# lp_breadboard_mini.net
KiCad netlist of a schematic drawn in EAGLE
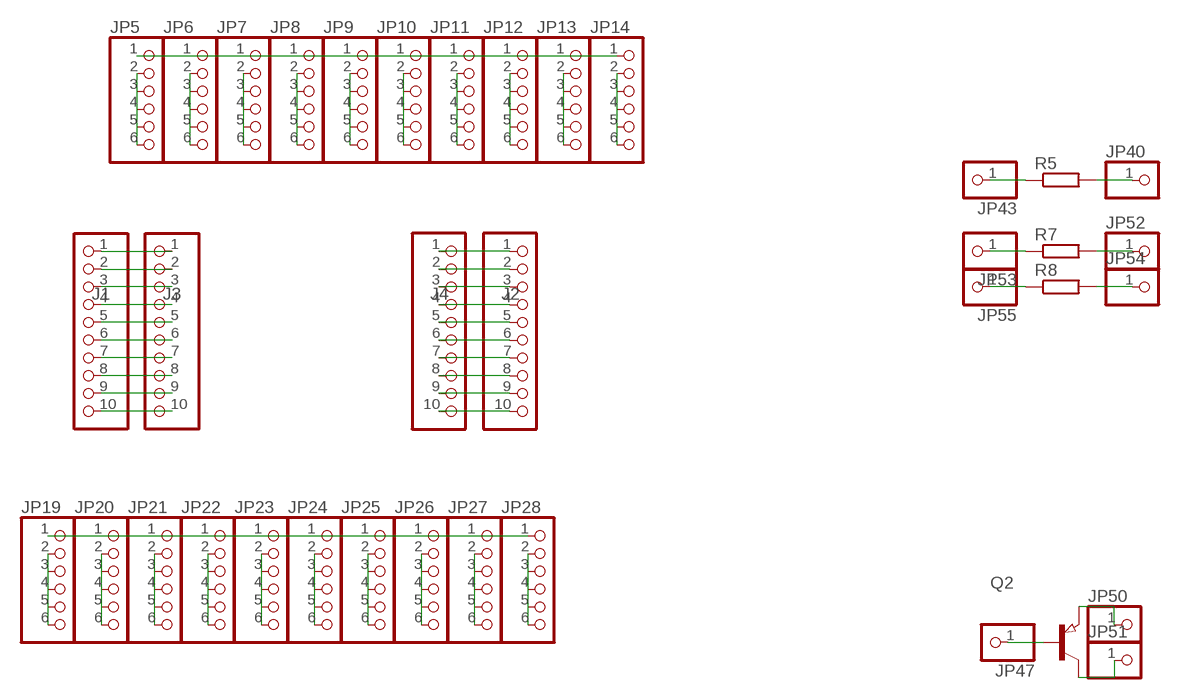
[diagram p0: schematic, sheet 1]

(export (version "E")
  (design (tool "Eeschema 10.0.6"))
  (components
    (comp (ref "J1")
      (value "PINHD-1X10")
      (footprint "eagle-import:1X10")
      (libsource (lib "eagle-import") (part "PINHD-1X10"))
    )
    (comp (ref "J2")
      (value "PINHD-1X10")
      (footprint "eagle-import:1X10")
      (libsource (lib "eagle-import") (part "PINHD-1X10"))
    )
    (comp (ref "J3")
      (value "PINHD-1X10")
      (footprint "eagle-import:1X10")
      (libsource (lib "eagle-import") (part "PINHD-1X10"))
    )
    (comp (ref "J4")
      (value "PINHD-1X10")
      (footprint "eagle-import:1X10")
      (libsource (lib "eagle-import") (part "PINHD-1X10"))
    )
    (comp (ref "JP5")
      (value "PINHD-1X6")
      (footprint "eagle-import:1X06")
      (libsource (lib "eagle-import") (part "PINHD-1X6"))
    )
    (comp (ref "JP6")
      (value "PINHD-1X6")
      (footprint "eagle-import:1X06")
      (libsource (lib "eagle-import") (part "PINHD-1X6"))
    )
    (comp (ref "JP7")
      (value "PINHD-1X6")
      (footprint "eagle-import:1X06")
      (libsource (lib "eagle-import") (part "PINHD-1X6"))
    )
    (comp (ref "JP8")
      (value "PINHD-1X6")
      (footprint "eagle-import:1X06")
      (libsource (lib "eagle-import") (part "PINHD-1X6"))
    )
    (comp (ref "JP9")
      (value "PINHD-1X6")
      (footprint "eagle-import:1X06")
      (libsource (lib "eagle-import") (part "PINHD-1X6"))
    )
    (comp (ref "JP10")
      (value "PINHD-1X6")
      (footprint "eagle-import:1X06")
      (libsource (lib "eagle-import") (part "PINHD-1X6"))
    )
    (comp (ref "JP11")
      (value "PINHD-1X6")
      (footprint "eagle-import:1X06")
      (libsource (lib "eagle-import") (part "PINHD-1X6"))
    )
    (comp (ref "JP12")
      (value "PINHD-1X6")
      (footprint "eagle-import:1X06")
      (libsource (lib "eagle-import") (part "PINHD-1X6"))
    )
    (comp (ref "JP13")
      (value "PINHD-1X6")
      (footprint "eagle-import:1X06")
      (libsource (lib "eagle-import") (part "PINHD-1X6"))
    )
    (comp (ref "JP14")
      (value "PINHD-1X6")
      (footprint "eagle-import:1X06")
      (libsource (lib "eagle-import") (part "PINHD-1X6"))
    )
    (comp (ref "JP19")
      (value "PINHD-1X6")
      (footprint "eagle-import:1X06")
      (libsource (lib "eagle-import") (part "PINHD-1X6"))
    )
    (comp (ref "JP20")
      (value "PINHD-1X6")
      (footprint "eagle-import:1X06")
      (libsource (lib "eagle-import") (part "PINHD-1X6"))
    )
    (comp (ref "JP21")
      (value "PINHD-1X6")
      (footprint "eagle-import:1X06")
      (libsource (lib "eagle-import") (part "PINHD-1X6"))
    )
    (comp (ref "JP22")
      (value "PINHD-1X6")
      (footprint "eagle-import:1X06")
      (libsource (lib "eagle-import") (part "PINHD-1X6"))
    )
    (comp (ref "JP23")
      (value "PINHD-1X6")
      (footprint "eagle-import:1X06")
      (libsource (lib "eagle-import") (part "PINHD-1X6"))
    )
    (comp (ref "JP24")
      (value "PINHD-1X6")
      (footprint "eagle-import:1X06")
      (libsource (lib "eagle-import") (part "PINHD-1X6"))
    )
    (comp (ref "JP25")
      (value "PINHD-1X6")
      (footprint "eagle-import:1X06")
      (libsource (lib "eagle-import") (part "PINHD-1X6"))
    )
    (comp (ref "JP26")
      (value "PINHD-1X6")
      (footprint "eagle-import:1X06")
      (libsource (lib "eagle-import") (part "PINHD-1X6"))
    )
    (comp (ref "JP27")
      (value "PINHD-1X6")
      (footprint "eagle-import:1X06")
      (libsource (lib "eagle-import") (part "PINHD-1X6"))
    )
    (comp (ref "JP28")
      (value "PINHD-1X6")
      (footprint "eagle-import:1X06")
      (libsource (lib "eagle-import") (part "PINHD-1X6"))
    )
    (comp (ref "JP40")
      (value "PINHD-1X1")
      (footprint "eagle-import:1X01")
      (libsource (lib "eagle-import") (part "PINHD-1X1"))
    )
    (comp (ref "JP43")
      (value "PINHD-1X1")
      (footprint "eagle-import:1X01")
      (libsource (lib "eagle-import") (part "PINHD-1X1"))
    )
    (comp (ref "JP47")
      (value "PINHD-1X1")
      (footprint "eagle-import:1X01")
      (libsource (lib "eagle-import") (part "PINHD-1X1"))
    )
    (comp (ref "JP50")
      (value "PINHD-1X1")
      (footprint "eagle-import:1X01")
      (libsource (lib "eagle-import") (part "PINHD-1X1"))
    )
    (comp (ref "JP51")
      (value "PINHD-1X1")
      (footprint "eagle-import:1X01")
      (libsource (lib "eagle-import") (part "PINHD-1X1"))
    )
    (comp (ref "JP52")
      (value "PINHD-1X1")
      (footprint "eagle-import:1X01")
      (libsource (lib "eagle-import") (part "PINHD-1X1"))
    )
    (comp (ref "JP53")
      (value "PINHD-1X1")
      (footprint "eagle-import:1X01")
      (libsource (lib "eagle-import") (part "PINHD-1X1"))
    )
    (comp (ref "JP54")
      (value "PINHD-1X1")
      (footprint "eagle-import:1X01")
      (libsource (lib "eagle-import") (part "PINHD-1X1"))
    )
    (comp (ref "JP55")
      (value "PINHD-1X1")
      (footprint "eagle-import:1X01")
      (libsource (lib "eagle-import") (part "PINHD-1X1"))
    )
    (comp (ref "Q2")
      (value "PNP-TRANSISTOR_SOT23")
      (footprint "eagle-import:SOT23")
      (libsource (lib "eagle-import") (part "PNP-TRANSISTOR_SOT23"))
    )
    (comp (ref "R5")
      (value "R-EU_R0805")
      (footprint "eagle-import:R0805")
      (libsource (lib "eagle-import") (part "R-EU_R0805"))
    )
    (comp (ref "R7")
      (value "R-EU_R0805")
      (footprint "eagle-import:R0805")
      (libsource (lib "eagle-import") (part "R-EU_R0805"))
    )
    (comp (ref "R8")
      (value "R-EU_R0805")
      (footprint "eagle-import:R0805")
      (libsource (lib "eagle-import") (part "R-EU_R0805"))
    )
  )
  (nets
    (net (code "1") (name "/GND") (class "Default")
      (node (ref "J2") (pin "1") (pinfunction "1_1") (pintype "passive"))
      (node (ref "J4") (pin "1") (pinfunction "1_1") (pintype "passive"))
      (node (ref "JP10") (pin "1") (pinfunction "1_1") (pintype "passive"))
      (node (ref "JP11") (pin "1") (pinfunction "1_1") (pintype "passive"))
      (node (ref "JP12") (pin "1") (pinfunction "1_1") (pintype "passive"))
      (node (ref "JP13") (pin "1") (pinfunction "1_1") (pintype "passive"))
      (node (ref "JP14") (pin "1") (pinfunction "1_1") (pintype "passive"))
      (node (ref "JP5") (pin "1") (pinfunction "1_1") (pintype "passive"))
      (node (ref "JP6") (pin "1") (pinfunction "1_1") (pintype "passive"))
      (node (ref "JP7") (pin "1") (pinfunction "1_1") (pintype "passive"))
      (node (ref "JP8") (pin "1") (pinfunction "1_1") (pintype "passive"))
      (node (ref "JP9") (pin "1") (pinfunction "1_1") (pintype "passive"))
    )
    (net (code "2") (name "/VCC") (class "Default")
      (node (ref "J1") (pin "1") (pinfunction "1_1") (pintype "passive"))
      (node (ref "J3") (pin "1") (pinfunction "1_1") (pintype "passive"))
      (node (ref "JP19") (pin "1") (pinfunction "1_1") (pintype "passive"))
      (node (ref "JP20") (pin "1") (pinfunction "1_1") (pintype "passive"))
      (node (ref "JP21") (pin "1") (pinfunction "1_1") (pintype "passive"))
      (node (ref "JP22") (pin "1") (pinfunction "1_1") (pintype "passive"))
      (node (ref "JP23") (pin "1") (pinfunction "1_1") (pintype "passive"))
      (node (ref "JP24") (pin "1") (pinfunction "1_1") (pintype "passive"))
      (node (ref "JP25") (pin "1") (pinfunction "1_1") (pintype "passive"))
      (node (ref "JP26") (pin "1") (pinfunction "1_1") (pintype "passive"))
      (node (ref "JP27") (pin "1") (pinfunction "1_1") (pintype "passive"))
      (node (ref "JP28") (pin "1") (pinfunction "1_1") (pintype "passive"))
    )
    (net (code "3") (name "Net-(J1-Pad2)") (class "Default")
      (node (ref "J1") (pin "2") (pinfunction "2_2") (pintype "passive"))
      (node (ref "J3") (pin "2") (pinfunction "2_2") (pintype "passive"))
    )
    (net (code "4") (name "Net-(J1-Pad3)") (class "Default")
      (node (ref "J1") (pin "3") (pinfunction "3_3") (pintype "passive"))
      (node (ref "J3") (pin "3") (pinfunction "3_3") (pintype "passive"))
    )
    (net (code "5") (name "Net-(J1-Pad4)") (class "Default")
      (node (ref "J1") (pin "4") (pinfunction "4_4") (pintype "passive"))
      (node (ref "J3") (pin "4") (pinfunction "4_4") (pintype "passive"))
    )
    (net (code "6") (name "Net-(J1-Pad5)") (class "Default")
      (node (ref "J1") (pin "5") (pinfunction "5_5") (pintype "passive"))
      (node (ref "J3") (pin "5") (pinfunction "5_5") (pintype "passive"))
    )
    (net (code "7") (name "Net-(J1-Pad6)") (class "Default")
      (node (ref "J1") (pin "6") (pinfunction "6_6") (pintype "passive"))
      (node (ref "J3") (pin "6") (pinfunction "6_6") (pintype "passive"))
    )
    (net (code "8") (name "Net-(J1-Pad7)") (class "Default")
      (node (ref "J1") (pin "7") (pinfunction "7_7") (pintype "passive"))
      (node (ref "J3") (pin "7") (pinfunction "7_7") (pintype "passive"))
    )
    (net (code "9") (name "Net-(J1-Pad8)") (class "Default")
      (node (ref "J1") (pin "8") (pinfunction "8_8") (pintype "passive"))
      (node (ref "J3") (pin "8") (pinfunction "8_8") (pintype "passive"))
    )
    (net (code "10") (name "Net-(J1-Pad9)") (class "Default")
      (node (ref "J1") (pin "9") (pinfunction "9_9") (pintype "passive"))
      (node (ref "J3") (pin "9") (pinfunction "9_9") (pintype "passive"))
    )
    (net (code "11") (name "Net-(J1-Pad10)") (class "Default")
      (node (ref "J1") (pin "10") (pinfunction "10_10") (pintype "passive"))
      (node (ref "J3") (pin "10") (pinfunction "10_10") (pintype "passive"))
    )
    (net (code "12") (name "Net-(J2-Pad2)") (class "Default")
      (node (ref "J2") (pin "2") (pinfunction "2_2") (pintype "passive"))
      (node (ref "J4") (pin "2") (pinfunction "2_2") (pintype "passive"))
    )
    (net (code "13") (name "Net-(J2-Pad3)") (class "Default")
      (node (ref "J2") (pin "3") (pinfunction "3_3") (pintype "passive"))
      (node (ref "J4") (pin "3") (pinfunction "3_3") (pintype "passive"))
    )
    (net (code "14") (name "Net-(J2-Pad4)") (class "Default")
      (node (ref "J2") (pin "4") (pinfunction "4_4") (pintype "passive"))
      (node (ref "J4") (pin "4") (pinfunction "4_4") (pintype "passive"))
    )
    (net (code "15") (name "Net-(J2-Pad5)") (class "Default")
      (node (ref "J2") (pin "5") (pinfunction "5_5") (pintype "passive"))
      (node (ref "J4") (pin "5") (pinfunction "5_5") (pintype "passive"))
    )
    (net (code "16") (name "Net-(J2-Pad6)") (class "Default")
      (node (ref "J2") (pin "6") (pinfunction "6_6") (pintype "passive"))
      (node (ref "J4") (pin "6") (pinfunction "6_6") (pintype "passive"))
    )
    (net (code "17") (name "Net-(J2-Pad7)") (class "Default")
      (node (ref "J2") (pin "7") (pinfunction "7_7") (pintype "passive"))
      (node (ref "J4") (pin "7") (pinfunction "7_7") (pintype "passive"))
    )
    (net (code "18") (name "Net-(J2-Pad8)") (class "Default")
      (node (ref "J2") (pin "8") (pinfunction "8_8") (pintype "passive"))
      (node (ref "J4") (pin "8") (pinfunction "8_8") (pintype "passive"))
    )
    (net (code "19") (name "Net-(J2-Pad9)") (class "Default")
      (node (ref "J2") (pin "9") (pinfunction "9_9") (pintype "passive"))
      (node (ref "J4") (pin "9") (pinfunction "9_9") (pintype "passive"))
    )
    (net (code "20") (name "Net-(J2-Pad10)") (class "Default")
      (node (ref "J2") (pin "10") (pinfunction "10_10") (pintype "passive"))
      (node (ref "J4") (pin "10") (pinfunction "10_10") (pintype "passive"))
    )
    (net (code "21") (name "Net-(JP5-Pad2)") (class "Default")
      (node (ref "JP5") (pin "2") (pinfunction "2_2") (pintype "passive"))
      (node (ref "JP5") (pin "3") (pinfunction "3_3") (pintype "passive"))
      (node (ref "JP5") (pin "4") (pinfunction "4_4") (pintype "passive"))
      (node (ref "JP5") (pin "5") (pinfunction "5_5") (pintype "passive"))
      (node (ref "JP5") (pin "6") (pinfunction "6_6") (pintype "passive"))
    )
    (net (code "22") (name "Net-(JP6-Pad2)") (class "Default")
      (node (ref "JP6") (pin "2") (pinfunction "2_2") (pintype "passive"))
      (node (ref "JP6") (pin "3") (pinfunction "3_3") (pintype "passive"))
      (node (ref "JP6") (pin "4") (pinfunction "4_4") (pintype "passive"))
      (node (ref "JP6") (pin "5") (pinfunction "5_5") (pintype "passive"))
      (node (ref "JP6") (pin "6") (pinfunction "6_6") (pintype "passive"))
    )
    (net (code "23") (name "Net-(JP7-Pad2)") (class "Default")
      (node (ref "JP7") (pin "2") (pinfunction "2_2") (pintype "passive"))
      (node (ref "JP7") (pin "3") (pinfunction "3_3") (pintype "passive"))
      (node (ref "JP7") (pin "4") (pinfunction "4_4") (pintype "passive"))
      (node (ref "JP7") (pin "5") (pinfunction "5_5") (pintype "passive"))
      (node (ref "JP7") (pin "6") (pinfunction "6_6") (pintype "passive"))
    )
    (net (code "24") (name "Net-(JP8-Pad2)") (class "Default")
      (node (ref "JP8") (pin "2") (pinfunction "2_2") (pintype "passive"))
      (node (ref "JP8") (pin "3") (pinfunction "3_3") (pintype "passive"))
      (node (ref "JP8") (pin "4") (pinfunction "4_4") (pintype "passive"))
      (node (ref "JP8") (pin "5") (pinfunction "5_5") (pintype "passive"))
      (node (ref "JP8") (pin "6") (pinfunction "6_6") (pintype "passive"))
    )
    (net (code "25") (name "Net-(JP9-Pad2)") (class "Default")
      (node (ref "JP9") (pin "2") (pinfunction "2_2") (pintype "passive"))
      (node (ref "JP9") (pin "3") (pinfunction "3_3") (pintype "passive"))
      (node (ref "JP9") (pin "4") (pinfunction "4_4") (pintype "passive"))
      (node (ref "JP9") (pin "5") (pinfunction "5_5") (pintype "passive"))
      (node (ref "JP9") (pin "6") (pinfunction "6_6") (pintype "passive"))
    )
    (net (code "26") (name "Net-(JP10-Pad2)") (class "Default")
      (node (ref "JP10") (pin "2") (pinfunction "2_2") (pintype "passive"))
      (node (ref "JP10") (pin "3") (pinfunction "3_3") (pintype "passive"))
      (node (ref "JP10") (pin "4") (pinfunction "4_4") (pintype "passive"))
      (node (ref "JP10") (pin "5") (pinfunction "5_5") (pintype "passive"))
      (node (ref "JP10") (pin "6") (pinfunction "6_6") (pintype "passive"))
    )
    (net (code "27") (name "Net-(JP11-Pad2)") (class "Default")
      (node (ref "JP11") (pin "2") (pinfunction "2_2") (pintype "passive"))
      (node (ref "JP11") (pin "3") (pinfunction "3_3") (pintype "passive"))
      (node (ref "JP11") (pin "4") (pinfunction "4_4") (pintype "passive"))
      (node (ref "JP11") (pin "5") (pinfunction "5_5") (pintype "passive"))
      (node (ref "JP11") (pin "6") (pinfunction "6_6") (pintype "passive"))
    )
    (net (code "28") (name "Net-(JP12-Pad2)") (class "Default")
      (node (ref "JP12") (pin "2") (pinfunction "2_2") (pintype "passive"))
      (node (ref "JP12") (pin "3") (pinfunction "3_3") (pintype "passive"))
      (node (ref "JP12") (pin "4") (pinfunction "4_4") (pintype "passive"))
      (node (ref "JP12") (pin "5") (pinfunction "5_5") (pintype "passive"))
      (node (ref "JP12") (pin "6") (pinfunction "6_6") (pintype "passive"))
    )
    (net (code "29") (name "Net-(JP13-Pad2)") (class "Default")
      (node (ref "JP13") (pin "2") (pinfunction "2_2") (pintype "passive"))
      (node (ref "JP13") (pin "3") (pinfunction "3_3") (pintype "passive"))
      (node (ref "JP13") (pin "4") (pinfunction "4_4") (pintype "passive"))
      (node (ref "JP13") (pin "5") (pinfunction "5_5") (pintype "passive"))
      (node (ref "JP13") (pin "6") (pinfunction "6_6") (pintype "passive"))
    )
    (net (code "30") (name "Net-(JP14-Pad2)") (class "Default")
      (node (ref "JP14") (pin "2") (pinfunction "2_2") (pintype "passive"))
      (node (ref "JP14") (pin "3") (pinfunction "3_3") (pintype "passive"))
      (node (ref "JP14") (pin "4") (pinfunction "4_4") (pintype "passive"))
      (node (ref "JP14") (pin "5") (pinfunction "5_5") (pintype "passive"))
      (node (ref "JP14") (pin "6") (pinfunction "6_6") (pintype "passive"))
    )
    (net (code "31") (name "Net-(JP19-Pad2)") (class "Default")
      (node (ref "JP19") (pin "2") (pinfunction "2_2") (pintype "passive"))
      (node (ref "JP19") (pin "3") (pinfunction "3_3") (pintype "passive"))
      (node (ref "JP19") (pin "4") (pinfunction "4_4") (pintype "passive"))
      (node (ref "JP19") (pin "5") (pinfunction "5_5") (pintype "passive"))
      (node (ref "JP19") (pin "6") (pinfunction "6_6") (pintype "passive"))
    )
    (net (code "32") (name "Net-(JP20-Pad2)") (class "Default")
      (node (ref "JP20") (pin "2") (pinfunction "2_2") (pintype "passive"))
      (node (ref "JP20") (pin "3") (pinfunction "3_3") (pintype "passive"))
      (node (ref "JP20") (pin "4") (pinfunction "4_4") (pintype "passive"))
      (node (ref "JP20") (pin "5") (pinfunction "5_5") (pintype "passive"))
      (node (ref "JP20") (pin "6") (pinfunction "6_6") (pintype "passive"))
    )
    (net (code "33") (name "Net-(JP21-Pad2)") (class "Default")
      (node (ref "JP21") (pin "2") (pinfunction "2_2") (pintype "passive"))
      (node (ref "JP21") (pin "3") (pinfunction "3_3") (pintype "passive"))
      (node (ref "JP21") (pin "4") (pinfunction "4_4") (pintype "passive"))
      (node (ref "JP21") (pin "5") (pinfunction "5_5") (pintype "passive"))
      (node (ref "JP21") (pin "6") (pinfunction "6_6") (pintype "passive"))
    )
    (net (code "34") (name "Net-(JP22-Pad2)") (class "Default")
      (node (ref "JP22") (pin "2") (pinfunction "2_2") (pintype "passive"))
      (node (ref "JP22") (pin "3") (pinfunction "3_3") (pintype "passive"))
      (node (ref "JP22") (pin "4") (pinfunction "4_4") (pintype "passive"))
      (node (ref "JP22") (pin "5") (pinfunction "5_5") (pintype "passive"))
      (node (ref "JP22") (pin "6") (pinfunction "6_6") (pintype "passive"))
    )
    (net (code "35") (name "Net-(JP23-Pad2)") (class "Default")
      (node (ref "JP23") (pin "2") (pinfunction "2_2") (pintype "passive"))
      (node (ref "JP23") (pin "3") (pinfunction "3_3") (pintype "passive"))
      (node (ref "JP23") (pin "4") (pinfunction "4_4") (pintype "passive"))
      (node (ref "JP23") (pin "5") (pinfunction "5_5") (pintype "passive"))
      (node (ref "JP23") (pin "6") (pinfunction "6_6") (pintype "passive"))
    )
    (net (code "36") (name "Net-(JP24-Pad2)") (class "Default")
      (node (ref "JP24") (pin "2") (pinfunction "2_2") (pintype "passive"))
      (node (ref "JP24") (pin "3") (pinfunction "3_3") (pintype "passive"))
      (node (ref "JP24") (pin "4") (pinfunction "4_4") (pintype "passive"))
      (node (ref "JP24") (pin "5") (pinfunction "5_5") (pintype "passive"))
      (node (ref "JP24") (pin "6") (pinfunction "6_6") (pintype "passive"))
    )
    (net (code "37") (name "Net-(JP25-Pad2)") (class "Default")
      (node (ref "JP25") (pin "2") (pinfunction "2_2") (pintype "passive"))
      (node (ref "JP25") (pin "3") (pinfunction "3_3") (pintype "passive"))
      (node (ref "JP25") (pin "4") (pinfunction "4_4") (pintype "passive"))
      (node (ref "JP25") (pin "5") (pinfunction "5_5") (pintype "passive"))
      (node (ref "JP25") (pin "6") (pinfunction "6_6") (pintype "passive"))
    )
    (net (code "38") (name "Net-(JP26-Pad2)") (class "Default")
      (node (ref "JP26") (pin "2") (pinfunction "2_2") (pintype "passive"))
      (node (ref "JP26") (pin "3") (pinfunction "3_3") (pintype "passive"))
      (node (ref "JP26") (pin "4") (pinfunction "4_4") (pintype "passive"))
      (node (ref "JP26") (pin "5") (pinfunction "5_5") (pintype "passive"))
      (node (ref "JP26") (pin "6") (pinfunction "6_6") (pintype "passive"))
    )
    (net (code "39") (name "Net-(JP27-Pad2)") (class "Default")
      (node (ref "JP27") (pin "2") (pinfunction "2_2") (pintype "passive"))
      (node (ref "JP27") (pin "3") (pinfunction "3_3") (pintype "passive"))
      (node (ref "JP27") (pin "4") (pinfunction "4_4") (pintype "passive"))
      (node (ref "JP27") (pin "5") (pinfunction "5_5") (pintype "passive"))
      (node (ref "JP27") (pin "6") (pinfunction "6_6") (pintype "passive"))
    )
    (net (code "40") (name "Net-(JP28-Pad2)") (class "Default")
      (node (ref "JP28") (pin "2") (pinfunction "2_2") (pintype "passive"))
      (node (ref "JP28") (pin "3") (pinfunction "3_3") (pintype "passive"))
      (node (ref "JP28") (pin "4") (pinfunction "4_4") (pintype "passive"))
      (node (ref "JP28") (pin "5") (pinfunction "5_5") (pintype "passive"))
      (node (ref "JP28") (pin "6") (pinfunction "6_6") (pintype "passive"))
    )
    (net (code "41") (name "Net-(JP40-Pad1)") (class "Default")
      (node (ref "JP40") (pin "1") (pinfunction "1_1") (pintype "passive"))
      (node (ref "R5") (pin "2") (pinfunction "2_2") (pintype "passive"))
    )
    (net (code "42") (name "Net-(JP43-Pad1)") (class "Default")
      (node (ref "JP43") (pin "1") (pinfunction "1_1") (pintype "passive"))
      (node (ref "R5") (pin "1") (pinfunction "1_1") (pintype "passive"))
    )
    (net (code "43") (name "Net-(JP52-Pad1)") (class "Default")
      (node (ref "JP52") (pin "1") (pinfunction "1_1") (pintype "passive"))
      (node (ref "R7") (pin "2") (pinfunction "2_2") (pintype "passive"))
    )
    (net (code "44") (name "Net-(JP53-Pad1)") (class "Default")
      (node (ref "JP53") (pin "1") (pinfunction "1_1") (pintype "passive"))
      (node (ref "R7") (pin "1") (pinfunction "1_1") (pintype "passive"))
    )
    (net (code "45") (name "Net-(JP54-Pad1)") (class "Default")
      (node (ref "JP54") (pin "1") (pinfunction "1_1") (pintype "passive"))
      (node (ref "R8") (pin "2") (pinfunction "2_2") (pintype "passive"))
    )
    (net (code "46") (name "Net-(JP55-Pad1)") (class "Default")
      (node (ref "JP55") (pin "1") (pinfunction "1_1") (pintype "passive"))
      (node (ref "R8") (pin "1") (pinfunction "1_1") (pintype "passive"))
    )
    (net (code "47") (name "Net-(Q2-B)") (class "Default")
      (node (ref "JP47") (pin "1") (pinfunction "1_1") (pintype "passive"))
      (node (ref "Q2") (pin "1") (pinfunction "B_1") (pintype "passive"))
    )
    (net (code "48") (name "Net-(Q2-C)") (class "Default")
      (node (ref "JP51") (pin "1") (pinfunction "1_1") (pintype "passive"))
      (node (ref "Q2") (pin "3") (pinfunction "C_3") (pintype "passive"))
    )
    (net (code "49") (name "Net-(Q2-E)") (class "Default")
      (node (ref "JP50") (pin "1") (pinfunction "1_1") (pintype "passive"))
      (node (ref "Q2") (pin "2") (pinfunction "E_2") (pintype "passive"))
    )
  )
)
